# DCI_ST_LINK_V2-1.net
KiCad netlist of a schematic drawn in Altium Designer
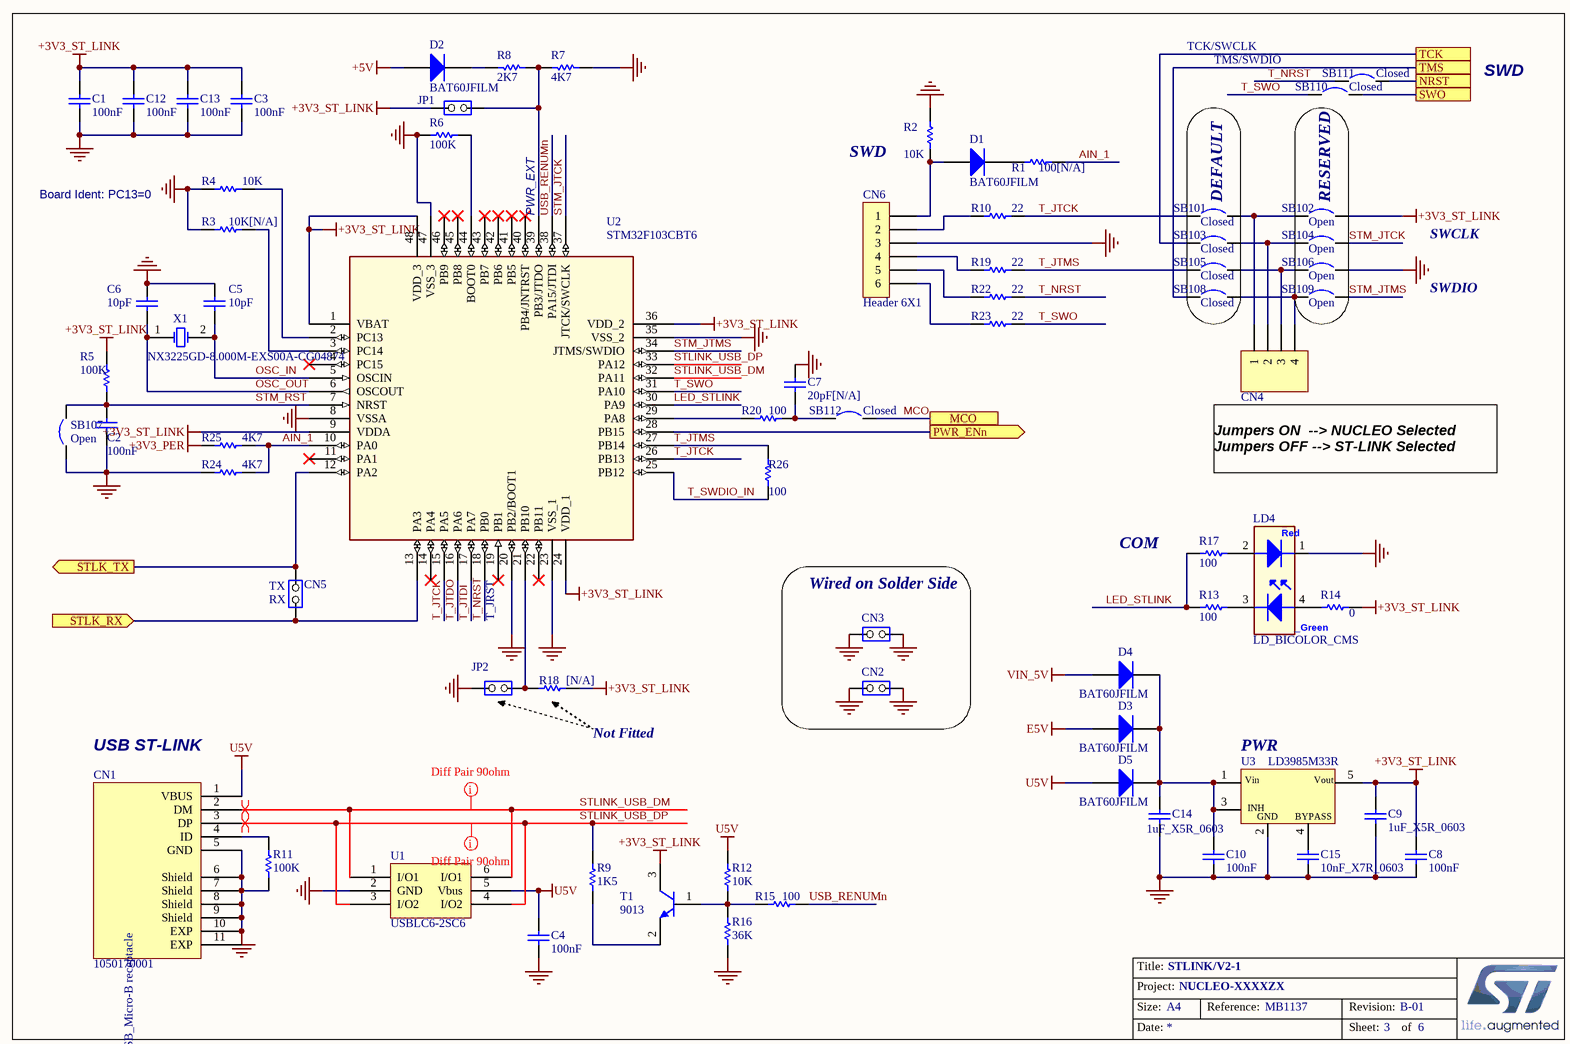
[diagram p0: DCI_ST_LINK_V2-1.SCHDOC]

(export (version "E")
  (design (tool "Eeschema 10.0.6"))
  (components
    (comp (ref "C1")
      (value "100nF")
      (footprint "0603C")
      (description "Capacitor 0402 / 0603 / 0805")
      (libsource (lib "MCD_TOOLS") (part "Capacitor_ST"))
    )
    (comp (ref "C2")
      (value "100nF")
      (footprint "0603C")
      (description "Capacitor 0402 / 0603 / 0805")
      (libsource (lib "MCD_TOOLS") (part "Capacitor_ST"))
    )
    (comp (ref "C3")
      (value "100nF")
      (footprint "0603C")
      (description "Capacitor 0402 / 0603 / 0805")
      (libsource (lib "MCD_TOOLS") (part "Capacitor_ST"))
    )
    (comp (ref "C4")
      (value "100nF")
      (footprint "0603C")
      (description "Capacitor 0402 / 0603 / 0805")
      (libsource (lib "MCD_TOOLS") (part "Capacitor_ST"))
    )
    (comp (ref "C5")
      (value "10pF")
      (footprint "0603C")
      (description "Capacitor 0402 / 0603 / 0805")
      (libsource (lib "MCD_TOOLS") (part "Capacitor_ST"))
    )
    (comp (ref "C6")
      (value "10pF")
      (footprint "0603C")
      (description "Capacitor 0402 / 0603 / 0805")
      (libsource (lib "MCD_TOOLS") (part "Capacitor_ST"))
    )
    (comp (ref "C7")
      (value "20pF[N/A]")
      (footprint "0603C")
      (description "Capacitor 0402 / 0603 / 0805")
      (libsource (lib "MCD_TOOLS") (part "Capacitor_ST"))
    )
    (comp (ref "C8")
      (value "100nF")
      (footprint "0603C")
      (description "Capacitor 0402 / 0603 / 0805")
      (libsource (lib "MCD_TOOLS") (part "Capacitor_ST"))
    )
    (comp (ref "C9")
      (value "1uF_X5R_0603")
      (footprint "0603C")
      (description "0603  X5R 1µF")
      (fields (field (name "TOLERANCE") "10%"))
      (libsource (lib "MB963_1") (part "CAP SMD 0603  X5R 1µF 25V 10%"))
    )
    (comp (ref "C10")
      (value "100nF")
      (footprint "0603C")
      (description "Capacitor 0402 / 0603 / 0805")
      (libsource (lib "MCD_TOOLS") (part "Capacitor_ST"))
    )
    (comp (ref "C12")
      (value "100nF")
      (footprint "0603C")
      (description "Capacitor 0402 / 0603 / 0805")
      (libsource (lib "MCD_TOOLS") (part "Capacitor_ST"))
    )
    (comp (ref "C13")
      (value "100nF")
      (footprint "0603C")
      (description "Capacitor 0402 / 0603 / 0805")
      (libsource (lib "MCD_TOOLS") (part "Capacitor_ST"))
    )
    (comp (ref "C14")
      (value "1uF_X5R_0603")
      (footprint "0603C")
      (description "0603  X5R 1µF")
      (fields (field (name "TOLERANCE") "10%"))
      (libsource (lib "MB963_1") (part "CAP SMD 0603  X5R 1µF 25V 10%"))
    )
    (comp (ref "C15")
      (value "10nF_X7R_0603")
      (footprint "0603C")
      (description "0603  X7R 10NF")
      (fields (field (name "TOLERANCE") "10%"))
      (libsource (lib "MB963_1") (part "CAP SMD 0603  X7R 10000PF 50V 10%"))
    )
    (comp (ref "CN1")
      (value "1050170001")
      (footprint "Molex_1050170001")
      (libsource (lib "Smartphone_accessory") (part "1050170001"))
    )
    (comp (ref "CN2") (value "~") (footprint "HDR_1x2_2R54_V_M") (libsource (lib "*") (part "JP2")))
    (comp (ref "CN3") (value "~") (footprint "HDR_1x2_2R54_V_M") (libsource (lib "*") (part "JP2")))
    (comp (ref "CN4")
      (value "Header 4")
      (footprint "HDR_1x4_2R54_V_M")
      (description "Header, 4-Pin, Single row")
      (fields (field (name "PUBLISHER") "Altium Limited"))
      (libsource (lib "Nucleo_64") (part "Header 4"))
    )
    (comp (ref "CN5") (value "~") (footprint "HDR_1x2_2R54_V_M_S") (libsource (lib "MCD_TOOLS") (part "JP2")))
    (comp (ref "CN6")
      (value "Header 6X1")
      (footprint "HDR_1x6_2R54_V_M")
      (description "Header, 6-Pin, Single row")
      (fields (field (name "PUBLISHER") "Altium Limited"))
      (libsource (lib "Nucleo_64") (part "Header 6X1"))
    )
    (comp (ref "D1")
      (value "BAT60JFILM")
      (footprint "SOD-323")
      (libsource (lib "MB1137") (part "BAT60JFILM"))
    )
    (comp (ref "D2")
      (value "BAT60JFILM")
      (footprint "SOD-323")
      (description "Default Diode")
      (fields (field (name "PUBLISHER") "Altium Limited"))
      (libsource (lib "MB1144_1") (part "Diode"))
    )
    (comp (ref "D3")
      (value "BAT60JFILM")
      (footprint "SOD-323")
      (libsource (lib "MB1137") (part "BAT60JFILM"))
    )
    (comp (ref "D4")
      (value "BAT60JFILM")
      (footprint "SOD-323")
      (libsource (lib "MB1137") (part "BAT60JFILM"))
    )
    (comp (ref "D5")
      (value "BAT60JFILM")
      (footprint "SOD-323")
      (libsource (lib "MB1137") (part "BAT60JFILM"))
    )
    (comp (ref "JP1") (value "~") (footprint "HDR_1x2_2R54_V_M_S") (libsource (lib "*") (part "JP2")))
    (comp (ref "JP2") (value "~") (footprint "HDR_1x2_2R54_V_M_S") (libsource (lib "*") (part "JP2")))
    (comp (ref "LD4")
      (value "LD_BICOLOR_CMS")
      (footprint "HSMF-A201")
      (description "Bicolor Led")
      (libsource (lib "MB1137") (part "LD_BICOLOR_CMS"))
    )
    (comp (ref "R1")
      (value "100[N/A]")
      (footprint "0603R")
      (description "Resistor 0402 / 0603 / 0805")
      (libsource (lib "Miscellaneous Devices") (part "Res1"))
    )
    (comp (ref "R2")
      (value "10K")
      (footprint "0603R")
      (description "Resistor 0402 / 0603 / 0805")
      (libsource (lib "Miscellaneous Devices") (part "Res1"))
    )
    (comp (ref "R3")
      (value "10K[N/A]")
      (footprint "0603R")
      (description "Resistor 0402 / 0603 / 0805")
      (libsource (lib "Miscellaneous Devices") (part "Res1"))
    )
    (comp (ref "R4")
      (value "10K")
      (footprint "0603R")
      (description "Resistor 0402 / 0603 / 0805")
      (libsource (lib "Miscellaneous Devices") (part "Res1"))
    )
    (comp (ref "R5")
      (value "100K")
      (footprint "0603R")
      (description "Resistor 0402 / 0603 / 0805")
      (libsource (lib "Miscellaneous Devices") (part "Res1"))
    )
    (comp (ref "R6")
      (value "100K")
      (footprint "0603R")
      (description "Resistor 0402 / 0603 / 0805")
      (libsource (lib "Miscellaneous Devices") (part "Res1"))
    )
    (comp (ref "R7")
      (value "4K7")
      (footprint "0603R")
      (description "Resistor")
      (fields (field (name "PUBLISHER") "Altium Limited"))
      (libsource (lib "") (part "Res1_2"))
    )
    (comp (ref "R8")
      (value "2K7")
      (footprint "0603R")
      (description "Resistor")
      (fields (field (name "PUBLISHER") "Altium Limited"))
      (libsource (lib "") (part "Res1_2"))
    )
    (comp (ref "R9")
      (value "1K5")
      (footprint "0603R")
      (description "Resistor 0402 / 0603 / 0805")
      (libsource (lib "Miscellaneous Devices") (part "Res1"))
    )
    (comp (ref "R10")
      (value "22")
      (footprint "0603R")
      (description "Resistor 0402 / 0603 / 0805")
      (libsource (lib "Miscellaneous Devices") (part "Res1"))
    )
    (comp (ref "R11")
      (value "100K")
      (footprint "0603R")
      (description "Resistor 0402 / 0603 / 0805")
      (libsource (lib "Miscellaneous Devices") (part "Res1"))
    )
    (comp (ref "R12")
      (value "10K")
      (footprint "0603R")
      (description "Resistor")
      (fields (field (name "PUBLISHER") "Altium Limited"))
      (libsource (lib "") (part "Res1_1"))
    )
    (comp (ref "R13")
      (value "100")
      (footprint "0603R")
      (description "Resistor 0402 / 0603 / 0805")
      (libsource (lib "Miscellaneous Devices") (part "Res1"))
    )
    (comp (ref "R14")
      (value "0")
      (footprint "0603R")
      (description "Resistor 0402 / 0603 / 0805")
      (libsource (lib "Miscellaneous Devices") (part "Res1"))
    )
    (comp (ref "R15")
      (value "100")
      (footprint "0603R")
      (description "Resistor 0402 / 0603 / 0805")
      (libsource (lib "Miscellaneous Devices") (part "Res1"))
    )
    (comp (ref "R16")
      (value "36K")
      (footprint "0603R")
      (description "Resistor")
      (fields (field (name "PUBLISHER") "Altium Limited"))
      (libsource (lib "") (part "Res1_1"))
    )
    (comp (ref "R17")
      (value "100")
      (footprint "0603R")
      (description "Resistor 0402 / 0603 / 0805")
      (libsource (lib "Miscellaneous Devices") (part "Res1"))
    )
    (comp (ref "R18")
      (value "[N/A]")
      (footprint "0603R")
      (description "Resistor")
      (fields (field (name "PUBLISHER") "Altium Limited"))
      (libsource (lib "") (part "Res1_1"))
    )
    (comp (ref "R19")
      (value "22")
      (footprint "0603R")
      (description "Resistor 0402 / 0603 / 0805")
      (libsource (lib "Miscellaneous Devices") (part "Res1"))
    )
    (comp (ref "R20")
      (value "100")
      (footprint "0603R")
      (description "Resistor 0402 / 0603 / 0805")
      (libsource (lib "Miscellaneous Devices") (part "Res1"))
    )
    (comp (ref "R22")
      (value "22")
      (footprint "0603R")
      (description "Resistor 0402 / 0603 / 0805")
      (libsource (lib "Miscellaneous Devices") (part "Res1"))
    )
    (comp (ref "R23")
      (value "22")
      (footprint "0603R")
      (description "Resistor 0402 / 0603 / 0805")
      (libsource (lib "Miscellaneous Devices") (part "Res1"))
    )
    (comp (ref "R24")
      (value "4K7")
      (footprint "0603R")
      (description "Resistor 0402 / 0603 / 0805")
      (libsource (lib "Miscellaneous Devices") (part "Res1"))
    )
    (comp (ref "R25")
      (value "4K7")
      (footprint "0603R")
      (description "Resistor 0402 / 0603 / 0805")
      (libsource (lib "Miscellaneous Devices") (part "Res1"))
    )
    (comp (ref "R26")
      (value "100")
      (footprint "0603R")
      (description "Resistor 0402 / 0603 / 0805")
      (libsource (lib "Miscellaneous Devices") (part "Res1"))
    )
    (comp (ref "SB101")
      (value "Closed")
      (footprint "SB_0603")
      (description "Circuit Breaker")
      (fields (field (name "PUBLISHER") "Altium Limited"))
      (libsource (lib "MB1167") (part "Circuit Breaker_close"))
    )
    (comp (ref "SB102")
      (value "Open")
      (footprint "SB_0603")
      (description "Circuit Breaker")
      (fields (field (name "PUBLISHER") "Altium Limited"))
      (libsource (lib "MB1167") (part "Circuit Breaker"))
    )
    (comp (ref "SB103")
      (value "Closed")
      (footprint "SB_0603")
      (description "Circuit Breaker")
      (fields (field (name "PUBLISHER") "Altium Limited"))
      (libsource (lib "MB1167") (part "Circuit Breaker_close"))
    )
    (comp (ref "SB104")
      (value "Open")
      (footprint "SB_0603")
      (description "Circuit Breaker")
      (fields (field (name "PUBLISHER") "Altium Limited"))
      (libsource (lib "MB1167") (part "Circuit Breaker"))
    )
    (comp (ref "SB105")
      (value "Closed")
      (footprint "SB_0603")
      (description "Circuit Breaker")
      (fields (field (name "PUBLISHER") "Altium Limited"))
      (libsource (lib "MB1167") (part "Circuit Breaker_close"))
    )
    (comp (ref "SB106")
      (value "Open")
      (footprint "SB_0603")
      (description "Circuit Breaker")
      (fields (field (name "PUBLISHER") "Altium Limited"))
      (libsource (lib "MB1167") (part "Circuit Breaker"))
    )
    (comp (ref "SB107")
      (value "Open")
      (footprint "SB_0603")
      (description "Circuit Breaker")
      (fields (field (name "PUBLISHER") "Altium Limited"))
      (libsource (lib "MB1167") (part "Circuit Breaker"))
    )
    (comp (ref "SB108")
      (value "Closed")
      (footprint "SB_0603")
      (description "Circuit Breaker")
      (fields (field (name "PUBLISHER") "Altium Limited"))
      (libsource (lib "MB1167") (part "Circuit Breaker_close"))
    )
    (comp (ref "SB109")
      (value "Open")
      (footprint "SB_0603")
      (description "Circuit Breaker")
      (fields (field (name "PUBLISHER") "Altium Limited"))
      (libsource (lib "MB1167") (part "Circuit Breaker"))
    )
    (comp (ref "SB110")
      (value "Closed")
      (footprint "SB_0603")
      (description "Circuit Breaker")
      (fields (field (name "PUBLISHER") "Altium Limited"))
      (libsource (lib "MB1167") (part "Circuit Breaker_close"))
    )
    (comp (ref "SB111")
      (value "Closed")
      (footprint "SB_0603")
      (description "Circuit Breaker")
      (fields (field (name "PUBLISHER") "Altium Limited"))
      (libsource (lib "MB1167") (part "Circuit Breaker_close"))
    )
    (comp (ref "SB112")
      (value "Closed")
      (footprint "SB_0603")
      (description "Circuit Breaker")
      (fields (field (name "PUBLISHER") "Altium Limited"))
      (libsource (lib "MB1167") (part "Circuit Breaker_close"))
    )
    (comp (ref "T1")
      (value "9013")
      (footprint "SOT-23")
      (description "NPN Bipolar Transistor")
      (fields (field (name "PUBLISHER") "Altium Limited"))
      (libsource (lib "MB1167") (part "NPN"))
    )
    (comp (ref "U1")
      (value "USBLC6-2SC6")
      (footprint "SOT23-6L")
      (libsource (lib "MB1137") (part "USBLC6-2SC6"))
    )
    (comp (ref "U2")
      (value "STM32F103CBT6")
      (footprint "LQFP48_0R5_7x7")
      (description "Medium-density performance line ARM-based 32-bit MCU with 64KB Flash")
      (libsource (lib "Nucleo_64") (part "STM32F103CBT6"))
    )
    (comp (ref "U3")
      (value "LD3985M33R")
      (footprint "SOT-23-5L")
      (description "Ultra low drop-low noise BiCMOS voltage, regulators low ESR capacitors compatible")
      (libsource (lib "MCD_TOOLS") (part "LD3985M33R"))
    )
    (comp (ref "X1")
      (value "NX3225GD-8.000M-EXS00A-CG04874")
      (footprint "OSC_2SM_3R2x2R5")
      (description "Crystal Oscillator")
      (fields (field (name "PUBLISHER") "Altium Limited"))
      (libsource (lib "MB963_1") (part "XTAL"))
    )
  )
  (nets
    (net (code "1") (name "+3V3_PER") (class "Default")
      (node (ref "R25") (pin "1") (pinfunction "1_1") (pintype "passive"))
    )
    (net (code "2") (name "+3V3_ST_LINK") (class "Default")
      (node (ref "C1") (pin "2") (pinfunction "2_2") (pintype "passive"))
      (node (ref "C12") (pin "2") (pinfunction "2_2") (pintype "passive"))
      (node (ref "C13") (pin "2") (pinfunction "2_2") (pintype "passive"))
      (node (ref "C3") (pin "2") (pinfunction "2_2") (pintype "passive"))
      (node (ref "C8") (pin "2") (pinfunction "2_2") (pintype "passive"))
      (node (ref "C9") (pin "1") (pinfunction "1_1") (pintype "passive"))
      (node (ref "JP1") (pin "1") (pinfunction "COMMON_1") (pintype "passive"))
      (node (ref "R14") (pin "2") (pinfunction "2_2") (pintype "passive"))
      (node (ref "R18") (pin "1") (pinfunction "1_1") (pintype "passive"))
      (node (ref "R5") (pin "2") (pinfunction "2_2") (pintype "passive"))
      (node (ref "SB102") (pin "2") (pinfunction "2_2") (pintype "passive"))
      (node (ref "T1") (pin "3") (pinfunction "C_3") (pintype "passive"))
      (node (ref "U2") (pin "1") (pinfunction "VBAT_1") (pintype "power_in"))
      (node (ref "U2") (pin "24") (pinfunction "VDD_1_24") (pintype "power_in"))
      (node (ref "U2") (pin "36") (pinfunction "VDD_2_36") (pintype "power_in"))
      (node (ref "U2") (pin "48") (pinfunction "VDD_3_48") (pintype "power_in"))
      (node (ref "U2") (pin "9") (pinfunction "VDDA_9") (pintype "power_in"))
      (node (ref "U3") (pin "5") (pinfunction "Vout_5") (pintype "passive"))
    )
    (net (code "3") (name "+5V") (class "Default")
      (node (ref "D2") (pin "1") (pinfunction "A_1") (pintype "passive"))
    )
    (net (code "4") (name "/AIN_1") (class "Default")
      (node (ref "R1") (pin "2") (pinfunction "2_2") (pintype "passive"))
      (node (ref "R24") (pin "2") (pinfunction "2_2") (pintype "passive"))
      (node (ref "R25") (pin "2") (pinfunction "2_2") (pintype "passive"))
      (node (ref "U2") (pin "10") (pinfunction "PA0_10") (pintype "bidirectional"))
    )
    (net (code "5") (name "/LED_STLINK") (class "Default")
      (node (ref "R13") (pin "1") (pinfunction "1_1") (pintype "passive"))
      (node (ref "R17") (pin "1") (pinfunction "1_1") (pintype "passive"))
      (node (ref "U2") (pin "30") (pinfunction "PA9_30") (pintype "bidirectional"))
    )
    (net (code "6") (name "/MCO") (class "Default")
      (node (ref "SB112") (pin "2") (pinfunction "2_2") (pintype "passive"))
    )
    (net (code "7") (name "/NRST") (class "Default")
      (node (ref "SB111") (pin "2") (pinfunction "2_2") (pintype "passive"))
    )
    (net (code "8") (name "/OSC_IN") (class "Default")
      (node (ref "C5") (pin "1") (pinfunction "1_1") (pintype "passive"))
      (node (ref "U2") (pin "5") (pinfunction "OSCIN_5") (pintype "input"))
      (node (ref "X1") (pin "2") (pinfunction "OSC2_2") (pintype "passive"))
    )
    (net (code "9") (name "/OSC_OUT") (class "Default")
      (node (ref "C6") (pin "1") (pinfunction "1_1") (pintype "passive"))
      (node (ref "U2") (pin "6") (pinfunction "OSCOUT_6") (pintype "output"))
      (node (ref "X1") (pin "1") (pinfunction "OSC1_1") (pintype "passive"))
    )
    (net (code "10") (name "/PWR_ENn") (class "Default")
      (node (ref "U2") (pin "28") (pinfunction "PB15_28") (pintype "bidirectional"))
    )
    (net (code "11") (name "/STLINK_USB_DM") (class "Default")
      (node (ref "CN1") (pin "2") (pinfunction "DM_2") (pintype "passive"))
      (node (ref "U1") (pin "1") (pinfunction "I/O1_1") (pintype "passive"))
      (node (ref "U1") (pin "6") (pinfunction "I/O1_6") (pintype "passive"))
      (node (ref "U2") (pin "32") (pinfunction "PA11_32") (pintype "bidirectional"))
    )
    (net (code "12") (name "/STLINK_USB_DP") (class "Default")
      (node (ref "CN1") (pin "3") (pinfunction "DP_3") (pintype "passive"))
      (node (ref "R9") (pin "1") (pinfunction "1_1") (pintype "passive"))
      (node (ref "U1") (pin "3") (pinfunction "I/O2_3") (pintype "passive"))
      (node (ref "U1") (pin "4") (pinfunction "I/O2_4") (pintype "passive"))
      (node (ref "U2") (pin "33") (pinfunction "PA12_33") (pintype "bidirectional"))
    )
    (net (code "13") (name "/STLK_RX") (class "Default")
      (node (ref "CN5") (pin "1") (pinfunction "COMMON_1") (pintype "passive"))
      (node (ref "U2") (pin "13") (pinfunction "PA3_13") (pintype "bidirectional"))
    )
    (net (code "14") (name "/STLK_TX") (class "Default")
      (node (ref "CN5") (pin "2") (pinfunction "NO_2") (pintype "passive"))
      (node (ref "U2") (pin "12") (pinfunction "PA2_12") (pintype "bidirectional"))
    )
    (net (code "15") (name "/STM_JTCK") (class "Default")
      (node (ref "SB104") (pin "2") (pinfunction "2_2") (pintype "passive"))
      (node (ref "U2") (pin "37") (pinfunction "JTCK/SWCLK_37") (pintype "bidirectional"))
    )
    (net (code "16") (name "/STM_JTMS") (class "Default")
      (node (ref "SB109") (pin "2") (pinfunction "2_2") (pintype "passive"))
      (node (ref "U2") (pin "34") (pinfunction "JTMS/SWDIO_34") (pintype "bidirectional"))
    )
    (net (code "17") (name "/STM_RST") (class "Default")
      (node (ref "C2") (pin "2") (pinfunction "2_2") (pintype "passive"))
      (node (ref "R5") (pin "1") (pinfunction "1_1") (pintype "passive"))
      (node (ref "SB107") (pin "2") (pinfunction "2_2") (pintype "passive"))
      (node (ref "U2") (pin "7") (pinfunction "NRST_7") (pintype "input"))
    )
    (net (code "18") (name "/SWO") (class "Default")
      (node (ref "SB110") (pin "2") (pinfunction "2_2") (pintype "passive"))
    )
    (net (code "19") (name "/TCK") (class "Default")
      (node (ref "SB103") (pin "1") (pinfunction "1_1") (pintype "passive"))
    )
    (net (code "20") (name "/TMS") (class "Default")
      (node (ref "SB108") (pin "1") (pinfunction "1_1") (pintype "passive"))
    )
    (net (code "21") (name "/T_JTCK") (class "Default")
      (node (ref "R10") (pin "2") (pinfunction "2_2") (pintype "passive"))
      (node (ref "SB101") (pin "1") (pinfunction "1_1") (pintype "passive"))
      (node (ref "U2") (pin "15") (pinfunction "PA5_15") (pintype "bidirectional"))
      (node (ref "U2") (pin "26") (pinfunction "PB13_26") (pintype "bidirectional"))
    )
    (net (code "22") (name "/T_JTDI") (class "Default")
      (node (ref "U2") (pin "17") (pinfunction "PA7_17") (pintype "bidirectional"))
    )
    (net (code "23") (name "/T_JTDO") (class "Default")
      (node (ref "U2") (pin "16") (pinfunction "PA6_16") (pintype "bidirectional"))
    )
    (net (code "24") (name "/T_JTMS") (class "Default")
      (node (ref "R19") (pin "2") (pinfunction "2_2") (pintype "passive"))
      (node (ref "R26") (pin "2") (pinfunction "2_2") (pintype "passive"))
      (node (ref "SB105") (pin "1") (pinfunction "1_1") (pintype "passive"))
      (node (ref "U2") (pin "27") (pinfunction "PB14_27") (pintype "bidirectional"))
    )
    (net (code "25") (name "/T_NRST") (class "Default")
      (node (ref "R22") (pin "2") (pinfunction "2_2") (pintype "passive"))
      (node (ref "SB111") (pin "1") (pinfunction "1_1") (pintype "passive"))
      (node (ref "U2") (pin "18") (pinfunction "PB0_18") (pintype "bidirectional"))
    )
    (net (code "26") (name "/T_SWDIO_IN") (class "Default")
      (node (ref "R26") (pin "1") (pinfunction "1_1") (pintype "passive"))
      (node (ref "U2") (pin "25") (pinfunction "PB12_25") (pintype "bidirectional"))
    )
    (net (code "27") (name "/T_SWO") (class "Default")
      (node (ref "R23") (pin "2") (pinfunction "2_2") (pintype "passive"))
      (node (ref "SB110") (pin "1") (pinfunction "1_1") (pintype "passive"))
      (node (ref "U2") (pin "31") (pinfunction "PA10_31") (pintype "bidirectional"))
    )
    (net (code "28") (name "/USB_RENUMn") (class "Default")
      (node (ref "R15") (pin "2") (pinfunction "2_2") (pintype "passive"))
      (node (ref "U2") (pin "38") (pinfunction "PA15/JTDI_38") (pintype "bidirectional"))
    )
    (net (code "29") (name "E5V") (class "Default")
      (node (ref "D3") (pin "1") (pinfunction "A_1") (pintype "passive"))
    )
    (net (code "30") (name "GND") (class "Default")
      (node (ref "C1") (pin "1") (pinfunction "1_1") (pintype "passive"))
      (node (ref "C10") (pin "1") (pinfunction "1_1") (pintype "passive"))
      (node (ref "C12") (pin "1") (pinfunction "1_1") (pintype "passive"))
      (node (ref "C13") (pin "1") (pinfunction "1_1") (pintype "passive"))
      (node (ref "C14") (pin "1") (pinfunction "1_1") (pintype "passive"))
      (node (ref "C15") (pin "1") (pinfunction "1_1") (pintype "passive"))
      (node (ref "C2") (pin "1") (pinfunction "1_1") (pintype "passive"))
      (node (ref "C3") (pin "1") (pinfunction "1_1") (pintype "passive"))
      (node (ref "C4") (pin "1") (pinfunction "1_1") (pintype "passive"))
      (node (ref "C5") (pin "2") (pinfunction "2_2") (pintype "passive"))
      (node (ref "C6") (pin "2") (pinfunction "2_2") (pintype "passive"))
      (node (ref "C7") (pin "2") (pinfunction "2_2") (pintype "passive"))
      (node (ref "C8") (pin "1") (pinfunction "1_1") (pintype "passive"))
      (node (ref "C9") (pin "2") (pinfunction "2_2") (pintype "passive"))
      (node (ref "CN1") (pin "10") (pinfunction "EXP_10") (pintype "passive"))
      (node (ref "CN1") (pin "5") (pinfunction "GND_5") (pintype "passive"))
      (node (ref "CN1") (pin "6") (pinfunction "Shield_6") (pintype "passive"))
      (node (ref "CN1") (pin "7") (pinfunction "Shield_7") (pintype "passive"))
      (node (ref "CN1") (pin "8") (pinfunction "Shield_8") (pintype "passive"))
      (node (ref "CN1") (pin "9") (pinfunction "Shield_9") (pintype "passive"))
      (node (ref "CN2") (pin "1") (pinfunction "COMMON_1") (pintype "passive"))
      (node (ref "CN2") (pin "2") (pinfunction "NO_2") (pintype "passive"))
      (node (ref "CN3") (pin "1") (pinfunction "COMMON_1") (pintype "passive"))
      (node (ref "CN3") (pin "2") (pinfunction "NO_2") (pintype "passive"))
      (node (ref "CN6") (pin "3") (pinfunction "3_3") (pintype "passive"))
      (node (ref "JP2") (pin "1") (pinfunction "COMMON_1") (pintype "passive"))
      (node (ref "LD4") (pin "1") (pinfunction "1_1") (pintype "passive"))
      (node (ref "R11") (pin "2") (pinfunction "2_2") (pintype "passive"))
      (node (ref "R16") (pin "1") (pinfunction "1_1") (pintype "passive"))
      (node (ref "R2") (pin "2") (pinfunction "2_2") (pintype "passive"))
      (node (ref "R24") (pin "1") (pinfunction "1_1") (pintype "passive"))
      (node (ref "R3") (pin "1") (pinfunction "1_1") (pintype "passive"))
      (node (ref "R4") (pin "1") (pinfunction "1_1") (pintype "passive"))
      (node (ref "R6") (pin "1") (pinfunction "1_1") (pintype "passive"))
      (node (ref "R7") (pin "2") (pinfunction "2_2") (pintype "passive"))
      (node (ref "SB106") (pin "2") (pinfunction "2_2") (pintype "passive"))
      (node (ref "SB107") (pin "1") (pinfunction "1_1") (pintype "passive"))
      (node (ref "U1") (pin "2") (pinfunction "GND_2") (pintype "passive"))
      (node (ref "U2") (pin "20") (pinfunction "PB2/BOOT1_20") (pintype "bidirectional"))
      (node (ref "U2") (pin "23") (pinfunction "VSS_1_23") (pintype "power_in"))
      (node (ref "U2") (pin "35") (pinfunction "VSS_2_35") (pintype "power_in"))
      (node (ref "U2") (pin "47") (pinfunction "VSS_3_47") (pintype "power_in"))
      (node (ref "U2") (pin "8") (pinfunction "VSSA_8") (pintype "power_in"))
      (node (ref "U3") (pin "2") (pinfunction "GND_2") (pintype "passive"))
    )
    (net (code "31") (name "Net-(C7-Pad1)") (class "Default")
      (node (ref "C7") (pin "1") (pinfunction "1_1") (pintype "passive"))
      (node (ref "R20") (pin "2") (pinfunction "2_2") (pintype "passive"))
      (node (ref "SB112") (pin "1") (pinfunction "1_1") (pintype "passive"))
    )
    (net (code "32") (name "Net-(CN1-ID)") (class "Default")
      (node (ref "CN1") (pin "4") (pinfunction "ID_4") (pintype "passive"))
      (node (ref "R11") (pin "1") (pinfunction "1_1") (pintype "passive"))
    )
    (net (code "33") (name "Net-(CN4-Pad1)") (class "Default")
      (node (ref "CN4") (pin "1") (pinfunction "1_1") (pintype "passive"))
      (node (ref "SB101") (pin "2") (pinfunction "2_2") (pintype "passive"))
      (node (ref "SB102") (pin "1") (pinfunction "1_1") (pintype "passive"))
    )
    (net (code "34") (name "Net-(CN4-Pad2)") (class "Default")
      (node (ref "CN4") (pin "2") (pinfunction "2_2") (pintype "passive"))
      (node (ref "SB103") (pin "2") (pinfunction "2_2") (pintype "passive"))
      (node (ref "SB104") (pin "1") (pinfunction "1_1") (pintype "passive"))
    )
    (net (code "35") (name "Net-(CN4-Pad3)") (class "Default")
      (node (ref "CN4") (pin "3") (pinfunction "3_3") (pintype "passive"))
      (node (ref "SB105") (pin "2") (pinfunction "2_2") (pintype "passive"))
      (node (ref "SB106") (pin "1") (pinfunction "1_1") (pintype "passive"))
    )
    (net (code "36") (name "Net-(CN4-Pad4)") (class "Default")
      (node (ref "CN4") (pin "4") (pinfunction "4_4") (pintype "passive"))
      (node (ref "SB108") (pin "2") (pinfunction "2_2") (pintype "passive"))
      (node (ref "SB109") (pin "1") (pinfunction "1_1") (pintype "passive"))
    )
    (net (code "37") (name "Net-(CN6-Pad2)") (class "Default")
      (node (ref "CN6") (pin "2") (pinfunction "2_2") (pintype "passive"))
      (node (ref "R10") (pin "1") (pinfunction "1_1") (pintype "passive"))
    )
    (net (code "38") (name "Net-(CN6-Pad4)") (class "Default")
      (node (ref "CN6") (pin "4") (pinfunction "4_4") (pintype "passive"))
      (node (ref "R19") (pin "1") (pinfunction "1_1") (pintype "passive"))
    )
    (net (code "39") (name "Net-(CN6-Pad5)") (class "Default")
      (node (ref "CN6") (pin "5") (pinfunction "5_5") (pintype "passive"))
      (node (ref "R22") (pin "1") (pinfunction "1_1") (pintype "passive"))
    )
    (net (code "40") (name "Net-(CN6-Pad6)") (class "Default")
      (node (ref "CN6") (pin "6") (pinfunction "6_6") (pintype "passive"))
      (node (ref "R23") (pin "1") (pinfunction "1_1") (pintype "passive"))
    )
    (net (code "41") (name "Net-(D1-A)") (class "Default")
      (node (ref "CN6") (pin "1") (pinfunction "1_1") (pintype "passive"))
      (node (ref "D1") (pin "1") (pinfunction "A_1") (pintype "passive"))
      (node (ref "R2") (pin "1") (pinfunction "1_1") (pintype "passive"))
    )
    (net (code "42") (name "Net-(D1-K)") (class "Default")
      (node (ref "D1") (pin "2") (pinfunction "K_2") (pintype "passive"))
      (node (ref "R1") (pin "1") (pinfunction "1_1") (pintype "passive"))
    )
    (net (code "43") (name "Net-(D2-K)") (class "Default")
      (node (ref "D2") (pin "2") (pinfunction "K_2") (pintype "passive"))
      (node (ref "R8") (pin "1") (pinfunction "1_1") (pintype "passive"))
    )
    (net (code "44") (name "Net-(D3-K)") (class "Default")
      (node (ref "C10") (pin "2") (pinfunction "2_2") (pintype "passive"))
      (node (ref "C14") (pin "2") (pinfunction "2_2") (pintype "passive"))
      (node (ref "D3") (pin "2") (pinfunction "K_2") (pintype "passive"))
      (node (ref "D4") (pin "2") (pinfunction "K_2") (pintype "passive"))
      (node (ref "D5") (pin "2") (pinfunction "K_2") (pintype "passive"))
      (node (ref "U3") (pin "1") (pinfunction "Vin_1") (pintype "passive"))
      (node (ref "U3") (pin "3") (pinfunction "CE_3") (pintype "passive"))
    )
    (net (code "45") (name "Net-(JP1-NO)") (class "Default")
      (node (ref "JP1") (pin "2") (pinfunction "NO_2") (pintype "passive"))
      (node (ref "R7") (pin "1") (pinfunction "1_1") (pintype "passive"))
      (node (ref "R8") (pin "2") (pinfunction "2_2") (pintype "passive"))
      (node (ref "U2") (pin "39") (pinfunction "PB3/JTDO_39") (pintype "bidirectional"))
    )
    (net (code "46") (name "Net-(JP2-NO)") (class "Default")
      (node (ref "JP2") (pin "2") (pinfunction "NO_2") (pintype "passive"))
      (node (ref "R18") (pin "2") (pinfunction "2_2") (pintype "passive"))
      (node (ref "U2") (pin "21") (pinfunction "PB10_21") (pintype "bidirectional"))
    )
    (net (code "47") (name "Net-(LD4-Pad2)") (class "Default")
      (node (ref "LD4") (pin "2") (pinfunction "2_2") (pintype "passive"))
      (node (ref "R17") (pin "2") (pinfunction "2_2") (pintype "passive"))
    )
    (net (code "48") (name "Net-(LD4-Pad3)") (class "Default")
      (node (ref "LD4") (pin "3") (pinfunction "3_3") (pintype "passive"))
      (node (ref "R13") (pin "2") (pinfunction "2_2") (pintype "passive"))
    )
    (net (code "49") (name "Net-(LD4-Pad4)") (class "Default")
      (node (ref "LD4") (pin "4") (pinfunction "4_4") (pintype "passive"))
      (node (ref "R14") (pin "1") (pinfunction "1_1") (pintype "passive"))
    )
    (net (code "50") (name "Net-(T1-B)") (class "Default")
      (node (ref "R12") (pin "1") (pinfunction "1_1") (pintype "passive"))
      (node (ref "R15") (pin "1") (pinfunction "1_1") (pintype "passive"))
      (node (ref "R16") (pin "2") (pinfunction "2_2") (pintype "passive"))
      (node (ref "T1") (pin "1") (pinfunction "B_1") (pintype "passive"))
    )
    (net (code "51") (name "Net-(T1-E)") (class "Default")
      (node (ref "R9") (pin "2") (pinfunction "2_2") (pintype "passive"))
      (node (ref "T1") (pin "2") (pinfunction "E_2") (pintype "passive"))
    )
    (net (code "52") (name "Net-(U2-BOOT0)") (class "Default")
      (node (ref "R6") (pin "2") (pinfunction "2_2") (pintype "passive"))
      (node (ref "U2") (pin "44") (pinfunction "BOOT0_44") (pintype "bidirectional"))
    )
    (net (code "53") (name "Net-(U2-PA8)") (class "Default")
      (node (ref "R20") (pin "1") (pinfunction "1_1") (pintype "passive"))
      (node (ref "U2") (pin "29") (pinfunction "PA8_29") (pintype "bidirectional"))
    )
    (net (code "54") (name "Net-(U2-PC13)") (class "Default")
      (node (ref "R4") (pin "2") (pinfunction "2_2") (pintype "passive"))
      (node (ref "U2") (pin "2") (pinfunction "PC13_2") (pintype "bidirectional"))
    )
    (net (code "55") (name "Net-(U2-PC14)") (class "Default")
      (node (ref "R3") (pin "2") (pinfunction "2_2") (pintype "passive"))
      (node (ref "U2") (pin "3") (pinfunction "PC14_3") (pintype "bidirectional"))
    )
    (net (code "56") (name "Net-(U3-BYPASS)") (class "Default")
      (node (ref "C15") (pin "2") (pinfunction "2_2") (pintype "passive"))
      (node (ref "U3") (pin "4") (pinfunction "BYPASS_4") (pintype "passive"))
    )
    (net (code "57") (name "U5V") (class "Default")
      (node (ref "C4") (pin "2") (pinfunction "2_2") (pintype "passive"))
      (node (ref "CN1") (pin "1") (pinfunction "VBUS_1") (pintype "passive"))
      (node (ref "D5") (pin "1") (pinfunction "A_1") (pintype "passive"))
      (node (ref "R12") (pin "2") (pinfunction "2_2") (pintype "passive"))
      (node (ref "U1") (pin "5") (pinfunction "Vbus_5") (pintype "passive"))
    )
    (net (code "58") (name "VIN_5V") (class "Default")
      (node (ref "D4") (pin "1") (pinfunction "A_1") (pintype "passive"))
    )
    (net (code "59") (name "unconnected-(CN1-EXP-Pad11)") (class "Default")
      (node (ref "CN1") (pin "11") (pinfunction "EXP_11") (pintype "passive"))
    )
    (net (code "60") (name "unconnected-(U2-PA1-Pad11)") (class "Default")
      (node (ref "U2") (pin "11") (pinfunction "PA1_11") (pintype "bidirectional+no_connect"))
    )
    (net (code "61") (name "unconnected-(U2-PA4-Pad14)") (class "Default")
      (node (ref "U2") (pin "14") (pinfunction "PA4_14") (pintype "bidirectional+no_connect"))
    )
    (net (code "62") (name "unconnected-(U2-PB1-Pad19)") (class "Default")
      (node (ref "U2") (pin "19") (pinfunction "PB1_19") (pintype "input+no_connect"))
    )
    (net (code "63") (name "unconnected-(U2-PB4{slash}JNTRST-Pad40)") (class "Default")
      (node (ref "U2") (pin "40") (pinfunction "PB4/JNTRST_40") (pintype "bidirectional+no_connect"))
    )
    (net (code "64") (name "unconnected-(U2-PB5-Pad41)") (class "Default")
      (node (ref "U2") (pin "41") (pinfunction "PB5_41") (pintype "bidirectional+no_connect"))
    )
    (net (code "65") (name "unconnected-(U2-PB6-Pad42)") (class "Default")
      (node (ref "U2") (pin "42") (pinfunction "PB6_42") (pintype "bidirectional+no_connect"))
    )
    (net (code "66") (name "unconnected-(U2-PB7-Pad43)") (class "Default")
      (node (ref "U2") (pin "43") (pinfunction "PB7_43") (pintype "bidirectional+no_connect"))
    )
    (net (code "67") (name "unconnected-(U2-PB8-Pad45)") (class "Default")
      (node (ref "U2") (pin "45") (pinfunction "PB8_45") (pintype "bidirectional+no_connect"))
    )
    (net (code "68") (name "unconnected-(U2-PB9-Pad46)") (class "Default")
      (node (ref "U2") (pin "46") (pinfunction "PB9_46") (pintype "bidirectional+no_connect"))
    )
    (net (code "69") (name "unconnected-(U2-PB11-Pad22)") (class "Default")
      (node (ref "U2") (pin "22") (pinfunction "PB11_22") (pintype "bidirectional+no_connect"))
    )
    (net (code "70") (name "unconnected-(U2-PC15-Pad4)") (class "Default")
      (node (ref "U2") (pin "4") (pinfunction "PC15_4") (pintype "bidirectional+no_connect"))
    )
  )
)
